# KeepUntil-v1_0_4.net
KiCad netlist of a schematic drawn in EAGLE
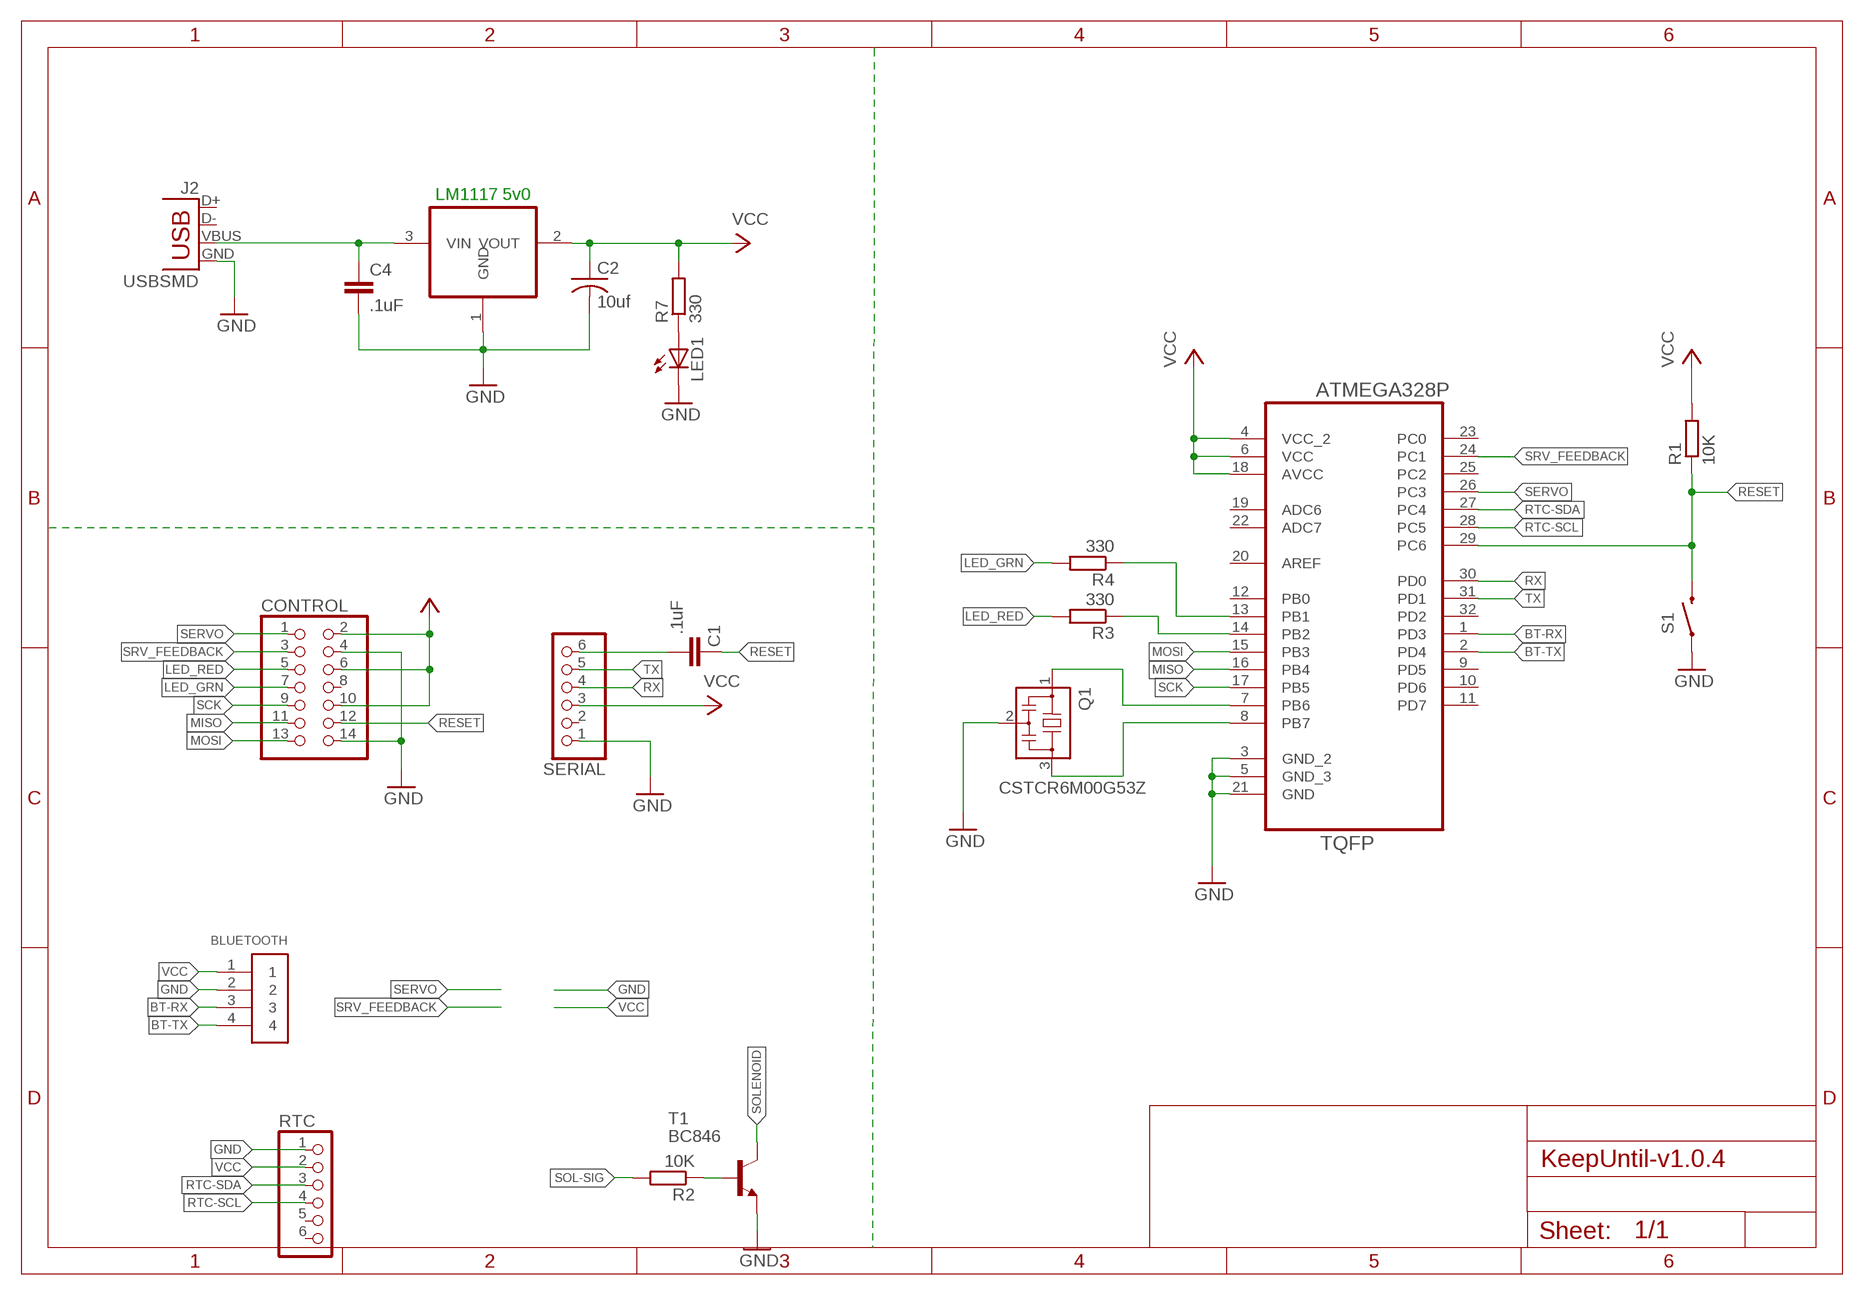
[diagram p0: schematic, sheet 1]

(export (version "E")
  (design (tool "Eeschema 10.0.6"))
  (components
    (comp (ref "BLUETOOTH")
      (value "1X4-CLEANBIG")
      (footprint "eagle-import:1X04-CLEANBIG")
      (libsource (lib "eagle-import") (part "1X4-CLEANBIG"))
    )
    (comp (ref "C1")
      (value ".1uF")
      (footprint "eagle-import:C0805")
      (libsource (lib "eagle-import") (part "C-EUC0805"))
    )
    (comp (ref "C2")
      (value "10uf")
      (footprint "eagle-import:C1206")
      (libsource (lib "eagle-import") (part "C-USC1206"))
    )
    (comp (ref "C4")
      (value ".1uF")
      (footprint "eagle-import:C0805")
      (libsource (lib "eagle-import") (part "C-EUC0805"))
    )
    (comp (ref "CONTROL")
      (value "PINHD-2X7")
      (footprint "eagle-import:2X07")
      (libsource (lib "eagle-import") (part "PINHD-2X7"))
    )
    (comp (ref "IC2")
      (value "REG1117")
      (footprint "eagle-import:SOT223")
      (fields (field (name "MPN") "LM1117 3v3"))
      (libsource (lib "eagle-import") (part "REG1117"))
    )
    (comp (ref "J2")
      (value "USBSMD")
      (footprint "eagle-import:USB-MINIB")
      (libsource (lib "eagle-import") (part "USBSMD"))
    )
    (comp (ref "LED1")
      (value "LEDSMT1206")
      (footprint "eagle-import:1206")
      (libsource (lib "eagle-import") (part "LEDSMT1206"))
    )
    (comp (ref "Q1")
      (value "CSTCR6M00G53Z")
      (footprint "eagle-import:CSTCR6M")
      (fields (field (name "MPN") "CSTCR6M00G53-R0"))
      (libsource (lib "eagle-import") (part "CSTCR6M00G53Z"))
    )
    (comp (ref "R1")
      (value "10K")
      (footprint "eagle-import:R0805")
      (libsource (lib "eagle-import") (part "R-EU_R0805"))
    )
    (comp (ref "R2")
      (value "10K")
      (footprint "eagle-import:R0805")
      (libsource (lib "eagle-import") (part "R-EU_R0805"))
    )
    (comp (ref "R3")
      (value "330")
      (footprint "eagle-import:R0805")
      (libsource (lib "eagle-import") (part "R-EU_R0805"))
    )
    (comp (ref "R4")
      (value "330")
      (footprint "eagle-import:R0805")
      (libsource (lib "eagle-import") (part "R-EU_R0805"))
    )
    (comp (ref "R7")
      (value "330")
      (footprint "eagle-import:R0805")
      (libsource (lib "eagle-import") (part "R-EU_R0805"))
    )
    (comp (ref "RTC")
      (value "PINHD-1X6CLEAN")
      (footprint "eagle-import:1X06-CLEAN")
      (libsource (lib "eagle-import") (part "PINHD-1X6CLEAN"))
    )
    (comp (ref "S1")
      (value "SWITCH-MOMENTARY-2SMD-1101NE")
      (footprint "eagle-import:TACTILE-SWITCH-1101NE")
      (libsource (lib "eagle-import") (part "SWITCH-MOMENTARY-2SMD-1101NE"))
    )
    (comp (ref "SERIAL")
      (value "PINHD-1X6CLEAN")
      (footprint "eagle-import:1X06-CLEAN")
      (libsource (lib "eagle-import") (part "PINHD-1X6CLEAN"))
    )
    (comp (ref "T1")
      (value "BC846")
      (footprint "eagle-import:SOT23")
      (libsource (lib "eagle-import") (part "BC846"))
    )
    (comp (ref "U1")
      (value "ATMEGA328P-AU")
      (footprint "eagle-import:QFP80P900X900X120-32N")
      (libsource (lib "eagle-import") (part "ATMEGA328P-AU"))
    )
  )
  (nets
    (net (code "1") (name "BT-RX") (class "Default")
      (node (ref "BLUETOOTH") (pin "3") (pinfunction "3_3") (pintype "bidirectional"))
      (node (ref "U1") (pin "1") (pinfunction "PD3_1") (pintype "bidirectional"))
    )
    (net (code "2") (name "BT-TX") (class "Default")
      (node (ref "BLUETOOTH") (pin "4") (pinfunction "4_4") (pintype "bidirectional"))
      (node (ref "U1") (pin "2") (pinfunction "PD4_2") (pintype "bidirectional"))
    )
    (net (code "3") (name "GND") (class "Default")
      (node (ref "BLUETOOTH") (pin "2") (pinfunction "2_2") (pintype "bidirectional"))
      (node (ref "C2") (pin "2") (pinfunction "2_2") (pintype "passive"))
      (node (ref "C4") (pin "2") (pinfunction "2_2") (pintype "passive"))
      (node (ref "CONTROL") (pin "14") (pinfunction "14_14") (pintype "passive"))
      (node (ref "CONTROL") (pin "4") (pinfunction "4_4") (pintype "passive"))
      (node (ref "IC2") (pin "1") (pinfunction "GND_1") (pintype "power_in"))
      (node (ref "J2") (pin "GND") (pinfunction "GND_GND") (pintype "bidirectional"))
      (node (ref "LED1") (pin "C") (pinfunction "C_C") (pintype "passive"))
      (node (ref "Q1") (pin "2") (pinfunction "2_2") (pintype "passive"))
      (node (ref "RTC") (pin "1") (pinfunction "1_1") (pintype "passive"))
      (node (ref "S1") (pin "1") (pinfunction "1_1") (pintype "passive"))
      (node (ref "SERIAL") (pin "1") (pinfunction "1_1") (pintype "passive"))
      (node (ref "T1") (pin "2") (pinfunction "E_2") (pintype "passive"))
      (node (ref "U1") (pin "21") (pinfunction "GND_21") (pintype "passive"))
      (node (ref "U1") (pin "3") (pinfunction "GND_2_3") (pintype "passive"))
      (node (ref "U1") (pin "5") (pinfunction "GND_3_5") (pintype "passive"))
    )
    (net (code "4") (name "LED_GRN") (class "Default")
      (node (ref "CONTROL") (pin "7") (pinfunction "7_7") (pintype "passive"))
      (node (ref "R4") (pin "2") (pinfunction "2_2") (pintype "passive"))
    )
    (net (code "5") (name "LED_RED") (class "Default")
      (node (ref "CONTROL") (pin "5") (pinfunction "5_5") (pintype "passive"))
      (node (ref "R3") (pin "2") (pinfunction "2_2") (pintype "passive"))
    )
    (net (code "6") (name "MISO") (class "Default")
      (node (ref "CONTROL") (pin "11") (pinfunction "11_11") (pintype "passive"))
      (node (ref "U1") (pin "16") (pinfunction "PB4_16") (pintype "bidirectional"))
    )
    (net (code "7") (name "MOSI") (class "Default")
      (node (ref "CONTROL") (pin "13") (pinfunction "13_13") (pintype "passive"))
      (node (ref "U1") (pin "15") (pinfunction "PB3_15") (pintype "bidirectional"))
    )
    (net (code "8") (name "Net-(C1-Pad2)") (class "Default")
      (node (ref "C1") (pin "2") (pinfunction "2_2") (pintype "passive"))
      (node (ref "SERIAL") (pin "6") (pinfunction "6_6") (pintype "passive"))
    )
    (net (code "9") (name "Net-(IC2-VIN)") (class "Default")
      (node (ref "C4") (pin "1") (pinfunction "1_1") (pintype "passive"))
      (node (ref "IC2") (pin "3") (pinfunction "VIN_3") (pintype "input"))
      (node (ref "J2") (pin "VBUS") (pinfunction "VBUS_VBUS") (pintype "bidirectional"))
    )
    (net (code "10") (name "Net-(LED1-PadA)") (class "Default")
      (node (ref "LED1") (pin "A") (pinfunction "A_A") (pintype "passive"))
      (node (ref "R7") (pin "1") (pinfunction "1_1") (pintype "passive"))
    )
    (net (code "11") (name "Net-(T1-B)") (class "Default")
      (node (ref "R2") (pin "1") (pinfunction "1_1") (pintype "passive"))
      (node (ref "T1") (pin "1") (pinfunction "B_1") (pintype "passive"))
    )
    (net (code "12") (name "Net-(U1-PB1)") (class "Default")
      (node (ref "R4") (pin "1") (pinfunction "1_1") (pintype "passive"))
      (node (ref "U1") (pin "13") (pinfunction "PB1_13") (pintype "bidirectional"))
    )
    (net (code "13") (name "Net-(U1-PB2)") (class "Default")
      (node (ref "R3") (pin "1") (pinfunction "1_1") (pintype "passive"))
      (node (ref "U1") (pin "14") (pinfunction "PB2_14") (pintype "bidirectional"))
    )
    (net (code "14") (name "Net-(U1-PB6)") (class "Default")
      (node (ref "Q1") (pin "1") (pinfunction "1_1") (pintype "passive"))
      (node (ref "U1") (pin "7") (pinfunction "PB6_7") (pintype "bidirectional"))
    )
    (net (code "15") (name "Net-(U1-PB7)") (class "Default")
      (node (ref "Q1") (pin "3") (pinfunction "3_3") (pintype "passive"))
      (node (ref "U1") (pin "8") (pinfunction "PB7_8") (pintype "bidirectional"))
    )
    (net (code "16") (name "RESET") (class "Default")
      (node (ref "C1") (pin "1") (pinfunction "1_1") (pintype "passive"))
      (node (ref "CONTROL") (pin "12") (pinfunction "12_12") (pintype "passive"))
      (node (ref "R1") (pin "1") (pinfunction "1_1") (pintype "passive"))
      (node (ref "S1") (pin "2") (pinfunction "2_2") (pintype "passive"))
      (node (ref "U1") (pin "29") (pinfunction "PC6_29") (pintype "bidirectional"))
    )
    (net (code "17") (name "RTC-SCL") (class "Default")
      (node (ref "RTC") (pin "4") (pinfunction "4_4") (pintype "passive"))
      (node (ref "U1") (pin "28") (pinfunction "PC5_28") (pintype "bidirectional"))
    )
    (net (code "18") (name "RTC-SDA") (class "Default")
      (node (ref "RTC") (pin "3") (pinfunction "3_3") (pintype "passive"))
      (node (ref "U1") (pin "27") (pinfunction "PC4_27") (pintype "bidirectional"))
    )
    (net (code "19") (name "RX") (class "Default")
      (node (ref "SERIAL") (pin "4") (pinfunction "4_4") (pintype "passive"))
      (node (ref "U1") (pin "30") (pinfunction "PD0_30") (pintype "bidirectional"))
    )
    (net (code "20") (name "SCK") (class "Default")
      (node (ref "CONTROL") (pin "9") (pinfunction "9_9") (pintype "passive"))
      (node (ref "U1") (pin "17") (pinfunction "PB5_17") (pintype "bidirectional"))
    )
    (net (code "21") (name "SERVO") (class "Default")
      (node (ref "CONTROL") (pin "1") (pinfunction "1_1") (pintype "passive"))
      (node (ref "U1") (pin "26") (pinfunction "PC3_26") (pintype "bidirectional"))
    )
    (net (code "22") (name "SOL-SIG") (class "Default")
      (node (ref "R2") (pin "2") (pinfunction "2_2") (pintype "passive"))
    )
    (net (code "23") (name "SOLENOID") (class "Default")
      (node (ref "T1") (pin "3") (pinfunction "C_3") (pintype "passive"))
    )
    (net (code "24") (name "SRV_FEEDBACK") (class "Default")
      (node (ref "CONTROL") (pin "3") (pinfunction "3_3") (pintype "passive"))
      (node (ref "U1") (pin "24") (pinfunction "PC1_24") (pintype "bidirectional"))
    )
    (net (code "25") (name "TX") (class "Default")
      (node (ref "SERIAL") (pin "5") (pinfunction "5_5") (pintype "passive"))
      (node (ref "U1") (pin "31") (pinfunction "PD1_31") (pintype "bidirectional"))
    )
    (net (code "26") (name "VCC") (class "Default")
      (node (ref "BLUETOOTH") (pin "1") (pinfunction "1_1") (pintype "bidirectional"))
      (node (ref "C2") (pin "1") (pinfunction "1_1") (pintype "passive"))
      (node (ref "CONTROL") (pin "10") (pinfunction "10_10") (pintype "passive"))
      (node (ref "CONTROL") (pin "2") (pinfunction "2_2") (pintype "passive"))
      (node (ref "CONTROL") (pin "6") (pinfunction "6_6") (pintype "passive"))
      (node (ref "IC2") (pin "2") (pinfunction "VOUT_2") (pintype "output"))
      (node (ref "R1") (pin "2") (pinfunction "2_2") (pintype "passive"))
      (node (ref "R7") (pin "2") (pinfunction "2_2") (pintype "passive"))
      (node (ref "RTC") (pin "2") (pinfunction "2_2") (pintype "passive"))
      (node (ref "SERIAL") (pin "3") (pinfunction "3_3") (pintype "passive"))
      (node (ref "U1") (pin "18") (pinfunction "AVCC_18") (pintype "power_in"))
      (node (ref "U1") (pin "4") (pinfunction "VCC_2_4") (pintype "power_in"))
      (node (ref "U1") (pin "6") (pinfunction "VCC_6") (pintype "power_in"))
    )
    (net (code "27") (name "unconnected-(CONTROL-Pad8)") (class "Default")
      (node (ref "CONTROL") (pin "8") (pinfunction "8_8") (pintype "passive"))
    )
    (net (code "28") (name "unconnected-(J2-PadD+)") (class "Default")
      (node (ref "J2") (pin "D+") (pinfunction "D+_D+") (pintype "bidirectional"))
    )
    (net (code "29") (name "unconnected-(J2-PadD-)") (class "Default")
      (node (ref "J2") (pin "D-") (pinfunction "D-_D-") (pintype "bidirectional"))
    )
    (net (code "30") (name "unconnected-(RTC-Pad5)") (class "Default")
      (node (ref "RTC") (pin "5") (pinfunction "5_5") (pintype "passive"))
    )
    (net (code "31") (name "unconnected-(RTC-Pad6)") (class "Default")
      (node (ref "RTC") (pin "6") (pinfunction "6_6") (pintype "passive"))
    )
    (net (code "32") (name "unconnected-(SERIAL-Pad2)") (class "Default")
      (node (ref "SERIAL") (pin "2") (pinfunction "2_2") (pintype "passive"))
    )
    (net (code "33") (name "unconnected-(U1-ADC6-Pad19)") (class "Default")
      (node (ref "U1") (pin "19") (pinfunction "ADC6_19") (pintype "input"))
    )
    (net (code "34") (name "unconnected-(U1-ADC7-Pad22)") (class "Default")
      (node (ref "U1") (pin "22") (pinfunction "ADC7_22") (pintype "input"))
    )
    (net (code "35") (name "unconnected-(U1-AREF-Pad20)") (class "Default")
      (node (ref "U1") (pin "20") (pinfunction "AREF_20") (pintype "input"))
    )
    (net (code "36") (name "unconnected-(U1-PB0-Pad12)") (class "Default")
      (node (ref "U1") (pin "12") (pinfunction "PB0_12") (pintype "bidirectional"))
    )
    (net (code "37") (name "unconnected-(U1-PC0-Pad23)") (class "Default")
      (node (ref "U1") (pin "23") (pinfunction "PC0_23") (pintype "bidirectional"))
    )
    (net (code "38") (name "unconnected-(U1-PC2-Pad25)") (class "Default")
      (node (ref "U1") (pin "25") (pinfunction "PC2_25") (pintype "bidirectional"))
    )
    (net (code "39") (name "unconnected-(U1-PD2-Pad32)") (class "Default")
      (node (ref "U1") (pin "32") (pinfunction "PD2_32") (pintype "bidirectional"))
    )
    (net (code "40") (name "unconnected-(U1-PD5-Pad9)") (class "Default")
      (node (ref "U1") (pin "9") (pinfunction "PD5_9") (pintype "bidirectional"))
    )
    (net (code "41") (name "unconnected-(U1-PD6-Pad10)") (class "Default")
      (node (ref "U1") (pin "10") (pinfunction "PD6_10") (pintype "bidirectional"))
    )
    (net (code "42") (name "unconnected-(U1-PD7-Pad11)") (class "Default")
      (node (ref "U1") (pin "11") (pinfunction "PD7_11") (pintype "bidirectional"))
    )
  )
)
